# PCM5102A.net
KiCad netlist of a schematic drawn in Altium Designer
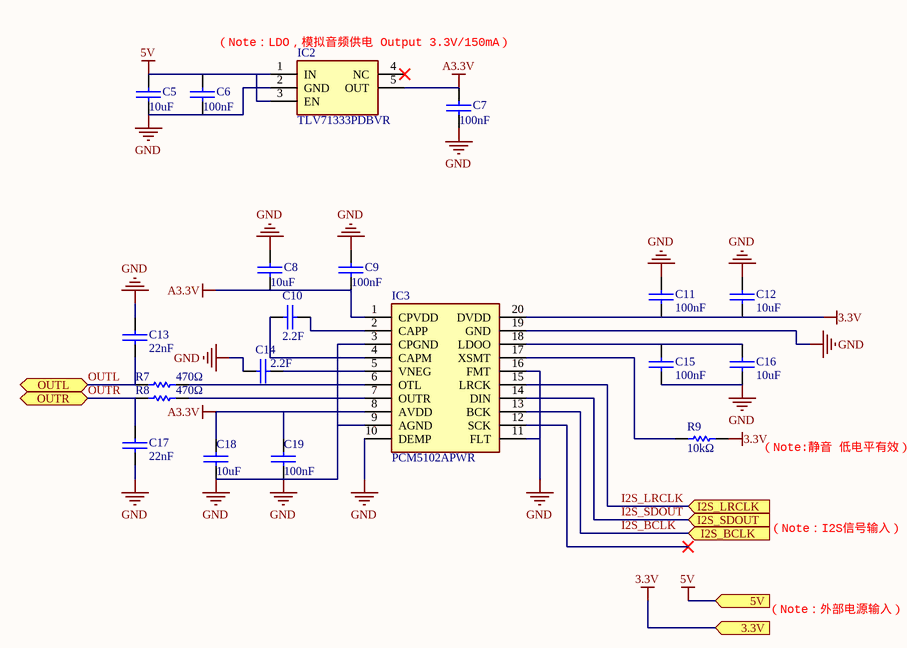
[diagram p0: PCM5102A.SchDoc]

(export (version "E")
  (design (tool "Eeschema 10.0.6"))
  (components
    (comp (ref "C5")
      (value "10uF")
      (footprint "C_0603")
      (description "贴片电容")
      (libsource (lib "IntLib-Passive") (part "Cap_Chip"))
    )
    (comp (ref "C6")
      (value "100nF")
      (footprint "C_0402")
      (description "贴片电容")
      (libsource (lib "IntLib-Passive") (part "Cap_Chip"))
    )
    (comp (ref "C7")
      (value "100nF")
      (footprint "C_0402")
      (description "贴片电容")
      (libsource (lib "IntLib-Passive") (part "Cap_Chip"))
    )
    (comp (ref "C8")
      (value "10uF")
      (footprint "C_0603")
      (description "贴片电容")
      (libsource (lib "IntLib-Passive") (part "Cap_Chip"))
    )
    (comp (ref "C9")
      (value "100nF")
      (footprint "C_0402")
      (description "贴片电容")
      (libsource (lib "IntLib-Passive") (part "Cap_Chip"))
    )
    (comp (ref "C10")
      (value "2.2F")
      (footprint "C_0402")
      (description "贴片电容")
      (libsource (lib "IntLib-Passive") (part "Cap_Chip"))
    )
    (comp (ref "C11")
      (value "100nF")
      (footprint "C_0402")
      (description "贴片电容")
      (libsource (lib "IntLib-Passive") (part "Cap_Chip"))
    )
    (comp (ref "C12")
      (value "10uF")
      (footprint "C_0603")
      (description "贴片电容")
      (libsource (lib "IntLib-Passive") (part "Cap_Chip"))
    )
    (comp (ref "C13")
      (value "22nF")
      (footprint "C_0402")
      (description "贴片电容")
      (libsource (lib "IntLib-Passive") (part "Cap_Chip"))
    )
    (comp (ref "C14")
      (value "2.2F")
      (footprint "C_0402")
      (description "贴片电容")
      (libsource (lib "IntLib-Passive") (part "Cap_Chip"))
    )
    (comp (ref "C15")
      (value "100nF")
      (footprint "C_0402")
      (description "贴片电容")
      (libsource (lib "IntLib-Passive") (part "Cap_Chip"))
    )
    (comp (ref "C16")
      (value "10uF")
      (footprint "C_0603")
      (description "贴片电容")
      (libsource (lib "IntLib-Passive") (part "Cap_Chip"))
    )
    (comp (ref "C17")
      (value "22nF")
      (footprint "C_0402")
      (description "贴片电容")
      (libsource (lib "IntLib-Passive") (part "Cap_Chip"))
    )
    (comp (ref "C18")
      (value "10uF")
      (footprint "C_0603")
      (description "贴片电容")
      (libsource (lib "IntLib-Passive") (part "Cap_Chip"))
    )
    (comp (ref "C19")
      (value "100nF")
      (footprint "C_0402")
      (description "贴片电容")
      (libsource (lib "IntLib-Passive") (part "Cap_Chip"))
    )
    (comp (ref "IC2")
      (value "TLV71333PDBVR")
      (footprint "SamacSys:SOT95P280X145-5N")
      (description "Integrated Circuit")
      (fields (field (name "MOUSER PART NUMBER") "595-TLV71333PDBVR"))
      (libsource (lib "*") (part "TLV71333PDBVR"))
    )
    (comp (ref "IC3")
      (value "PCM5102APWR")
      (footprint "SamacSys:SOP65P640X120-20N")
      (description "Integrated Circuit")
      (fields (field (name "MOUSER PART NUMBER") "595-PCM5102APWR"))
      (libsource (lib "*") (part "PCM5102APWR"))
    )
    (comp (ref "R7")
      (value "470Ω")
      (footprint "R_0402")
      (description "贴片电阻")
      (libsource (lib "IntLib-Passive") (part "Res_Chip"))
    )
    (comp (ref "R8")
      (value "470Ω")
      (footprint "R_0402")
      (description "贴片电阻")
      (libsource (lib "IntLib-Passive") (part "Res_Chip"))
    )
    (comp (ref "R9")
      (value "10kΩ")
      (footprint "R_0402")
      (description "贴片电阻")
      (libsource (lib "IntLib-Passive") (part "Res_Chip"))
    )
  )
  (nets
    (net (code "1") (name "/I2S_BCLK") (class "Default")
      (node (ref "IC3") (pin "13") (pinfunction "BCK_13") (pintype "passive"))
    )
    (net (code "2") (name "/I2S_LRCLK") (class "Default")
      (node (ref "IC3") (pin "15") (pinfunction "LRCK_15") (pintype "passive"))
    )
    (net (code "3") (name "/I2S_SDOUT") (class "Default")
      (node (ref "IC3") (pin "14") (pinfunction "DIN_14") (pintype "passive"))
    )
    (net (code "4") (name "/OUTL") (class "Default")
      (node (ref "C13") (pin "1") (pinfunction "1_1") (pintype "passive"))
      (node (ref "R7") (pin "2") (pinfunction "2_2") (pintype "passive"))
    )
    (net (code "5") (name "/OUTR") (class "Default")
      (node (ref "C17") (pin "2") (pinfunction "2_2") (pintype "passive"))
      (node (ref "R8") (pin "2") (pinfunction "2_2") (pintype "passive"))
    )
    (net (code "6") (name "3.3V") (class "Default")
      (node (ref "C11") (pin "1") (pinfunction "1_1") (pintype "passive"))
      (node (ref "C12") (pin "1") (pinfunction "1_1") (pintype "passive"))
      (node (ref "IC3") (pin "20") (pinfunction "DVDD_20") (pintype "passive"))
      (node (ref "R9") (pin "1") (pinfunction "1_1") (pintype "passive"))
    )
    (net (code "7") (name "5V") (class "Default")
      (node (ref "C5") (pin "2") (pinfunction "2_2") (pintype "passive"))
      (node (ref "C6") (pin "2") (pinfunction "2_2") (pintype "passive"))
      (node (ref "IC2") (pin "1") (pinfunction "IN_1") (pintype "passive"))
      (node (ref "IC2") (pin "3") (pinfunction "EN_3") (pintype "passive"))
    )
    (net (code "8") (name "A3.3V") (class "Default")
      (node (ref "C18") (pin "2") (pinfunction "2_2") (pintype "passive"))
      (node (ref "C19") (pin "2") (pinfunction "2_2") (pintype "passive"))
      (node (ref "C7") (pin "2") (pinfunction "2_2") (pintype "passive"))
      (node (ref "C8") (pin "1") (pinfunction "1_1") (pintype "passive"))
      (node (ref "C9") (pin "1") (pinfunction "1_1") (pintype "passive"))
      (node (ref "IC2") (pin "5") (pinfunction "OUT_5") (pintype "passive"))
      (node (ref "IC3") (pin "1") (pinfunction "CPVDD_1") (pintype "passive"))
      (node (ref "IC3") (pin "8") (pinfunction "AVDD_8") (pintype "passive"))
    )
    (net (code "9") (name "GND") (class "Default")
      (node (ref "C11") (pin "2") (pinfunction "2_2") (pintype "passive"))
      (node (ref "C12") (pin "2") (pinfunction "2_2") (pintype "passive"))
      (node (ref "C13") (pin "2") (pinfunction "2_2") (pintype "passive"))
      (node (ref "C14") (pin "2") (pinfunction "2_2") (pintype "passive"))
      (node (ref "C15") (pin "1") (pinfunction "1_1") (pintype "passive"))
      (node (ref "C16") (pin "1") (pinfunction "1_1") (pintype "passive"))
      (node (ref "C17") (pin "1") (pinfunction "1_1") (pintype "passive"))
      (node (ref "C18") (pin "1") (pinfunction "1_1") (pintype "passive"))
      (node (ref "C19") (pin "1") (pinfunction "1_1") (pintype "passive"))
      (node (ref "C5") (pin "1") (pinfunction "1_1") (pintype "passive"))
      (node (ref "C6") (pin "1") (pinfunction "1_1") (pintype "passive"))
      (node (ref "C7") (pin "1") (pinfunction "1_1") (pintype "passive"))
      (node (ref "C8") (pin "2") (pinfunction "2_2") (pintype "passive"))
      (node (ref "C9") (pin "2") (pinfunction "2_2") (pintype "passive"))
      (node (ref "IC2") (pin "2") (pinfunction "GND_2") (pintype "passive"))
      (node (ref "IC3") (pin "10") (pinfunction "DEMP_10") (pintype "passive"))
      (node (ref "IC3") (pin "11") (pinfunction "FLT_11") (pintype "passive"))
      (node (ref "IC3") (pin "16") (pinfunction "FMT_16") (pintype "passive"))
      (node (ref "IC3") (pin "19") (pinfunction "GND_19") (pintype "passive"))
      (node (ref "IC3") (pin "3") (pinfunction "CPGND_3") (pintype "passive"))
      (node (ref "IC3") (pin "9") (pinfunction "AGND_9") (pintype "passive"))
    )
    (net (code "10") (name "Net-(IC3-CAPM)") (class "Default")
      (node (ref "C10") (pin "2") (pinfunction "2_2") (pintype "passive"))
      (node (ref "IC3") (pin "4") (pinfunction "CAPM_4") (pintype "passive"))
    )
    (net (code "11") (name "Net-(IC3-CAPP)") (class "Default")
      (node (ref "C10") (pin "1") (pinfunction "1_1") (pintype "passive"))
      (node (ref "IC3") (pin "2") (pinfunction "CAPP_2") (pintype "passive"))
    )
    (net (code "12") (name "Net-(IC3-LDOO)") (class "Default")
      (node (ref "C15") (pin "2") (pinfunction "2_2") (pintype "passive"))
      (node (ref "C16") (pin "2") (pinfunction "2_2") (pintype "passive"))
      (node (ref "IC3") (pin "18") (pinfunction "LDOO_18") (pintype "passive"))
    )
    (net (code "13") (name "Net-(IC3-OTL)") (class "Default")
      (node (ref "IC3") (pin "6") (pinfunction "OTL_6") (pintype "passive"))
      (node (ref "R7") (pin "1") (pinfunction "1_1") (pintype "passive"))
    )
    (net (code "14") (name "Net-(IC3-OUTR)") (class "Default")
      (node (ref "IC3") (pin "7") (pinfunction "OUTR_7") (pintype "passive"))
      (node (ref "R8") (pin "1") (pinfunction "1_1") (pintype "passive"))
    )
    (net (code "15") (name "Net-(IC3-VNEG)") (class "Default")
      (node (ref "C14") (pin "1") (pinfunction "1_1") (pintype "passive"))
      (node (ref "IC3") (pin "5") (pinfunction "VNEG_5") (pintype "passive"))
    )
    (net (code "16") (name "Net-(IC3-XSMT)") (class "Default")
      (node (ref "IC3") (pin "17") (pinfunction "XSMT_17") (pintype "passive"))
      (node (ref "R9") (pin "2") (pinfunction "2_2") (pintype "passive"))
    )
    (net (code "17") (name "unconnected-(IC2-NC-Pad4)") (class "Default")
      (node (ref "IC2") (pin "4") (pinfunction "NC_4") (pintype "passive+no_connect"))
    )
    (net (code "18") (name "unconnected-(IC3-SCK-Pad12)") (class "Default")
      (node (ref "IC3") (pin "12") (pinfunction "SCK_12") (pintype "passive+no_connect"))
    )
  )
)
